# FPGA_FLASH_EEPROM.net
KiCad netlist of a schematic drawn in Altium Designer
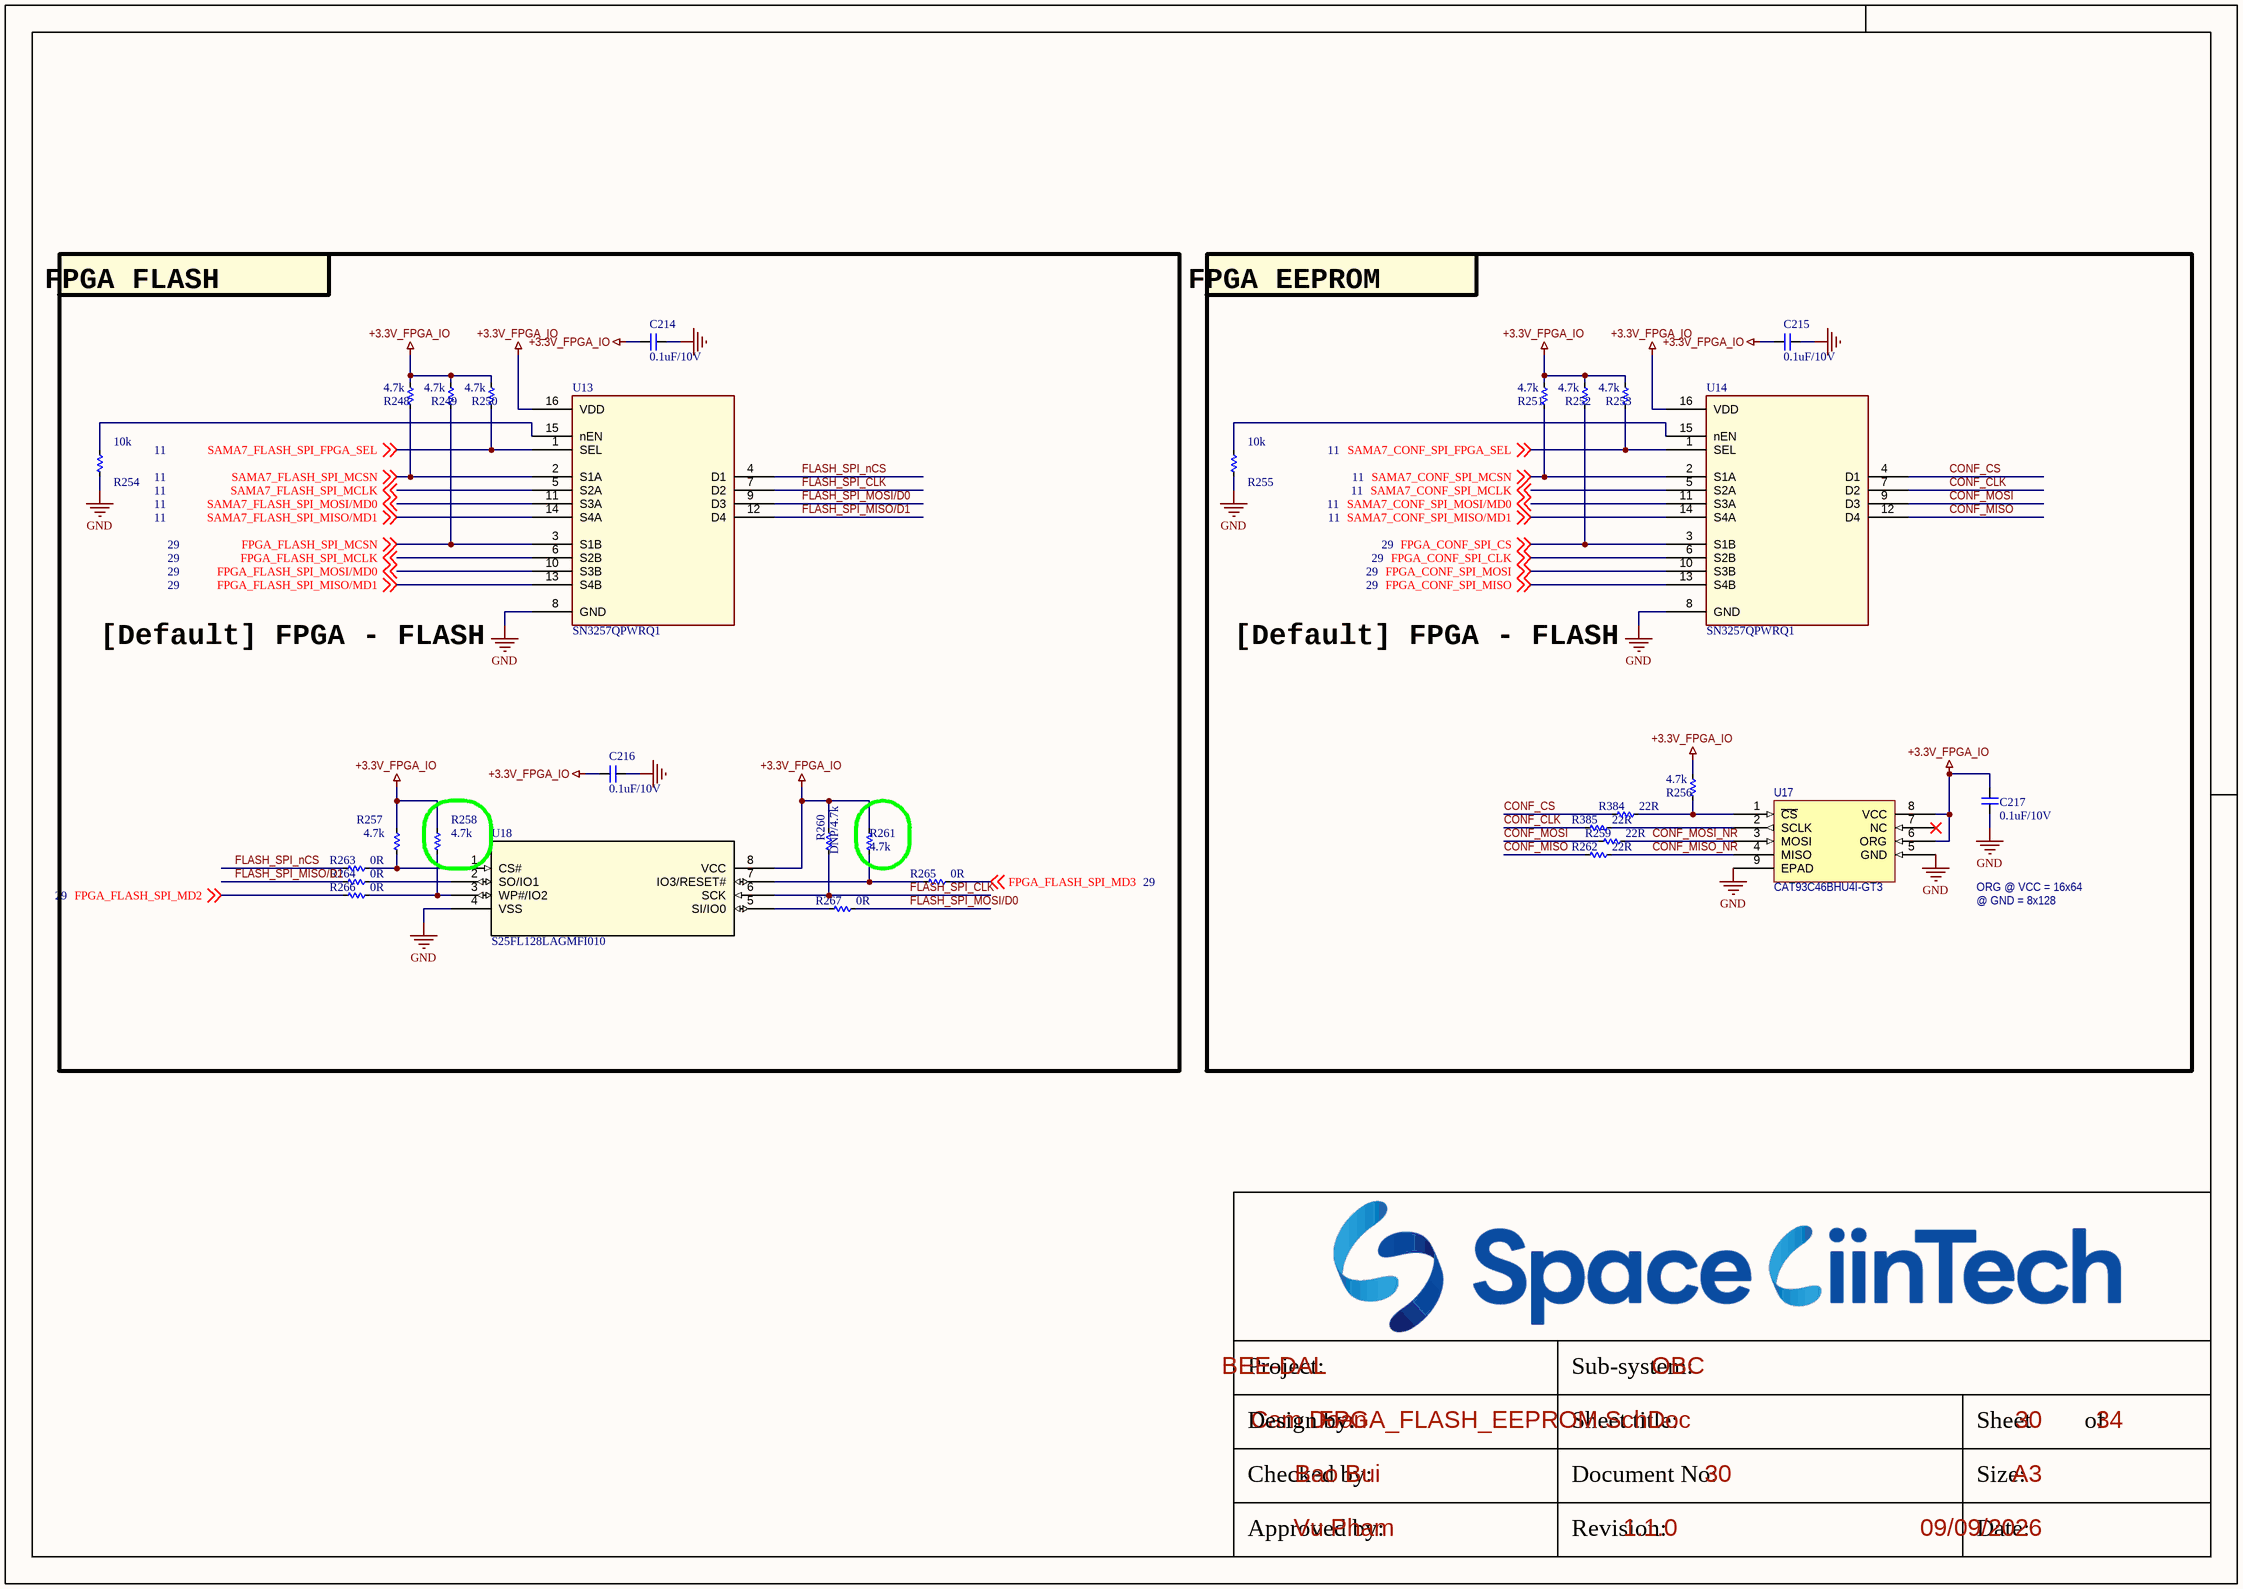
[diagram p0: FPGA_FLASH_EEPROM.SchDoc]

(export (version "E")
  (design (tool "Eeschema 10.0.6"))
  (components
    (comp (ref "C214")
      (value "0.1uF/10V")
      (footprint "CAP_C_1005X50_L")
      (description "CAP")
      (libsource (lib "LABLIB") (part "_CAP_C_2"))
    )
    (comp (ref "C215")
      (value "0.1uF/10V")
      (footprint "CAP_C_1005X50_L")
      (description "CAP")
      (libsource (lib "LABLIB") (part "_CAP_C_2"))
    )
    (comp (ref "C216")
      (value "0.1uF/10V")
      (footprint "CAP_C_1005X50_L")
      (description "CAP")
      (libsource (lib "LABLIB") (part "_CAP_C_2"))
    )
    (comp (ref "C217")
      (value "0.1uF/10V")
      (footprint "CAP_C_1005X50_L")
      (description "CAP")
      (libsource (lib "LABLIB") (part "_CAP_C_2"))
    )
    (comp (ref "R248")
      (value "4.7k")
      (footprint "RES_C_1005x30_L")
      (description "RES")
      (libsource (lib "IFBschelib") (part "_RES_B_2"))
    )
    (comp (ref "R249")
      (value "4.7k")
      (footprint "RES_C_1005x30_L")
      (description "RES")
      (libsource (lib "IFBschelib") (part "_RES_B_2"))
    )
    (comp (ref "R250")
      (value "4.7k")
      (footprint "RES_C_1005x30_L")
      (description "RES")
      (libsource (lib "IFBschelib") (part "_RES_B_2"))
    )
    (comp (ref "R251")
      (value "4.7k")
      (footprint "RES_C_1005x30_L")
      (description "RES")
      (libsource (lib "IFBschelib") (part "_RES_B_2"))
    )
    (comp (ref "R252")
      (value "4.7k")
      (footprint "RES_C_1005x30_L")
      (description "RES")
      (libsource (lib "IFBschelib") (part "_RES_B_2"))
    )
    (comp (ref "R253")
      (value "4.7k")
      (footprint "RES_C_1005x30_L")
      (description "RES")
      (libsource (lib "IFBschelib") (part "_RES_B_2"))
    )
    (comp (ref "R254")
      (value "10k")
      (footprint "RES_C_1005x30_L")
      (description "RES")
      (libsource (lib "LABLIB") (part "_RES_B_2"))
    )
    (comp (ref "R255")
      (value "10k")
      (footprint "RES_C_1005x30_L")
      (description "RES")
      (libsource (lib "LABLIB") (part "_RES_B_2"))
    )
    (comp (ref "R256")
      (value "4.7k")
      (footprint "RES_C_1005x30_L")
      (description "RES")
      (libsource (lib "IFBschelib") (part "_RES_B_2"))
    )
    (comp (ref "R257")
      (value "4.7k")
      (footprint "RES_C_1005x30_L")
      (description "RES")
      (libsource (lib "IFBschelib") (part "_RES_B_2"))
    )
    (comp (ref "R258")
      (value "4.7k")
      (footprint "RES_C_1005x30_L")
      (description "RES")
      (libsource (lib "IFBschelib") (part "_RES_B_2"))
    )
    (comp (ref "R259")
      (value "22R")
      (footprint "RES_C_1005x30_L")
      (description "RES")
      (libsource (lib "IFBschelib") (part "_RES_B_2"))
    )
    (comp (ref "R260")
      (value "DNP/4.7k")
      (footprint "RES_C_1005x30_L")
      (description "RES")
      (libsource (lib "IFBschelib") (part "_RES_B_2"))
    )
    (comp (ref "R261")
      (value "4.7k")
      (footprint "RES_C_1005x30_L")
      (description "RES")
      (libsource (lib "IFBschelib") (part "_RES_B_2"))
    )
    (comp (ref "R262")
      (value "22R")
      (footprint "RES_C_1005x30_L")
      (description "RES")
      (libsource (lib "IFBschelib") (part "_RES_B_2"))
    )
    (comp (ref "R263")
      (value "0R")
      (footprint "RES_C_1005x30_L")
      (description "RES")
      (libsource (lib "LABLIB") (part "_RES_B_2"))
    )
    (comp (ref "R264")
      (value "0R")
      (footprint "RES_C_1005x30_L")
      (description "RES")
      (libsource (lib "LABLIB") (part "_RES_B_2"))
    )
    (comp (ref "R265")
      (value "0R")
      (footprint "RES_C_1005x30_L")
      (description "RES")
      (libsource (lib "LABLIB") (part "_RES_B_2"))
    )
    (comp (ref "R266")
      (value "0R")
      (footprint "RES_C_1005x30_L")
      (description "RES")
      (libsource (lib "LABLIB") (part "_RES_B_2"))
    )
    (comp (ref "R267")
      (value "0R")
      (footprint "RES_C_1005x30_L")
      (description "RES")
      (libsource (lib "LABLIB") (part "_RES_B_2"))
    )
    (comp (ref "R384")
      (value "22R")
      (footprint "RES_C_1005x30_L")
      (description "RES")
      (libsource (lib "IFBschelib") (part "_RES_B_2"))
    )
    (comp (ref "R385")
      (value "22R")
      (footprint "RES_C_1005x30_L")
      (description "RES")
      (libsource (lib "IFBschelib") (part "_RES_B_2"))
    )
    (comp (ref "U13")
      (value "SN3257QPWRQ1")
      (footprint "SOIC_PRQ1_TEX")
      (fields (field (name "COPYRIGHT") "Copyright (C) 2025 Ultra Librarian. All rights reserved."))
      (libsource (lib "LABLIB") (part "IC_SW_SPI_SN3257QPWRQ1"))
    )
    (comp (ref "U14")
      (value "SN3257QPWRQ1")
      (footprint "SOIC_PRQ1_TEX")
      (fields (field (name "COPYRIGHT") "Copyright (C) 2025 Ultra Librarian. All rights reserved."))
      (libsource (lib "LABLIB") (part "IC_SW_SPI_SN3257QPWRQ1"))
    )
    (comp (ref "U17")
      (value "CAT93C46BHU4I-GT3")
      (footprint "CAT93C46BHU4I-GT3")
      (description "EEPROM Memory IC 1Kb (128 x 8, 64 x 16) SPI 4 MHz 8-UDFN-EP (2x3)")
      (libsource (lib "Virtex") (part "CAT93C46BHU4I-GT3"))
    )
    (comp (ref "U18")
      (value "S25FL128LAGMFI010")
      (footprint "SOIC8_S25FL_CYP")
      (description "Description")
      (fields (field (name "COPYRIGHT") "Copyright (C) 2025 Ultra Librarian. All rights reserved."))
      (libsource (lib "IFBschelib") (part "S25FL128LAGMFI010"))
    )
  )
  (nets
    (net (code "1") (name "+3.3V_FPGA_IO") (class "Default")
      (node (ref "C214") (pin "2") (pinfunction "2_2") (pintype "passive"))
      (node (ref "C215") (pin "2") (pinfunction "2_2") (pintype "passive"))
      (node (ref "C216") (pin "2") (pinfunction "2_2") (pintype "passive"))
      (node (ref "C217") (pin "1") (pinfunction "1_1") (pintype "passive"))
      (node (ref "R248") (pin "2") (pinfunction "2_2") (pintype "passive"))
      (node (ref "R249") (pin "2") (pinfunction "2_2") (pintype "passive"))
      (node (ref "R250") (pin "2") (pinfunction "2_2") (pintype "passive"))
      (node (ref "R251") (pin "2") (pinfunction "2_2") (pintype "passive"))
      (node (ref "R252") (pin "2") (pinfunction "2_2") (pintype "passive"))
      (node (ref "R253") (pin "2") (pinfunction "2_2") (pintype "passive"))
      (node (ref "R256") (pin "2") (pinfunction "2_2") (pintype "passive"))
      (node (ref "R257") (pin "2") (pinfunction "2_2") (pintype "passive"))
      (node (ref "R258") (pin "2") (pinfunction "2_2") (pintype "passive"))
      (node (ref "R260") (pin "2") (pinfunction "2_2") (pintype "passive"))
      (node (ref "R261") (pin "2") (pinfunction "2_2") (pintype "passive"))
      (node (ref "U13") (pin "16") (pinfunction "VDD_16") (pintype "passive"))
      (node (ref "U14") (pin "16") (pinfunction "VDD_16") (pintype "passive"))
      (node (ref "U17") (pin "6") (pinfunction "ORG_6") (pintype "input"))
      (node (ref "U17") (pin "8") (pinfunction "VCC_8") (pintype "power_in"))
      (node (ref "U18") (pin "8") (pinfunction "VCC_8") (pintype "power_in"))
    )
    (net (code "2") (name "/CONF_CLK") (class "Default")
      (node (ref "R385") (pin "2") (pinfunction "2_2") (pintype "passive"))
      (node (ref "U14") (pin "7") (pinfunction "D2_7") (pintype "passive"))
    )
    (net (code "3") (name "/CONF_CS") (class "Default")
      (node (ref "R384") (pin "2") (pinfunction "2_2") (pintype "passive"))
      (node (ref "U14") (pin "4") (pinfunction "D1_4") (pintype "passive"))
    )
    (net (code "4") (name "/CONF_MISO") (class "Default")
      (node (ref "R262") (pin "2") (pinfunction "2_2") (pintype "passive"))
      (node (ref "U14") (pin "12") (pinfunction "D4_12") (pintype "passive"))
    )
    (net (code "5") (name "/CONF_MISO_NR") (class "Default")
      (node (ref "R262") (pin "1") (pinfunction "1_1") (pintype "passive"))
      (node (ref "U17") (pin "4") (pinfunction "MISO_4") (pintype "power_in"))
    )
    (net (code "6") (name "/CONF_MOSI") (class "Default")
      (node (ref "R259") (pin "2") (pinfunction "2_2") (pintype "passive"))
      (node (ref "U14") (pin "9") (pinfunction "D3_9") (pintype "passive"))
    )
    (net (code "7") (name "/CONF_MOSI_NR") (class "Default")
      (node (ref "R259") (pin "1") (pinfunction "1_1") (pintype "passive"))
      (node (ref "U17") (pin "3") (pinfunction "MOSI_3") (pintype "input"))
    )
    (net (code "8") (name "/FLASH_SPI_CLK") (class "Default")
      (node (ref "R260") (pin "1") (pinfunction "1_1") (pintype "passive"))
      (node (ref "U13") (pin "7") (pinfunction "D2_7") (pintype "passive"))
      (node (ref "U18") (pin "6") (pinfunction "SCK_6") (pintype "input"))
    )
    (net (code "9") (name "/FLASH_SPI_MISO{slash}D1") (class "Default")
      (node (ref "R264") (pin "1") (pinfunction "1_1") (pintype "passive"))
      (node (ref "U13") (pin "12") (pinfunction "D4_12") (pintype "passive"))
    )
    (net (code "10") (name "/FLASH_SPI_MOSI{slash}D0") (class "Default")
      (node (ref "R267") (pin "2") (pinfunction "2_2") (pintype "passive"))
      (node (ref "U13") (pin "9") (pinfunction "D3_9") (pintype "passive"))
    )
    (net (code "11") (name "/FLASH_SPI_nCS") (class "Default")
      (node (ref "R263") (pin "1") (pinfunction "1_1") (pintype "passive"))
      (node (ref "U13") (pin "4") (pinfunction "D1_4") (pintype "passive"))
    )
    (net (code "12") (name "FPGA_CONF_SPI_CLK") (class "Default")
      (node (ref "U14") (pin "6") (pinfunction "S2B_6") (pintype "passive"))
    )
    (net (code "13") (name "FPGA_CONF_SPI_CS") (class "Default")
      (node (ref "R252") (pin "1") (pinfunction "1_1") (pintype "passive"))
      (node (ref "U14") (pin "3") (pinfunction "S1B_3") (pintype "passive"))
    )
    (net (code "14") (name "FPGA_CONF_SPI_MISO") (class "Default")
      (node (ref "U14") (pin "13") (pinfunction "S4B_13") (pintype "passive"))
    )
    (net (code "15") (name "FPGA_CONF_SPI_MOSI") (class "Default")
      (node (ref "U14") (pin "10") (pinfunction "S3B_10") (pintype "passive"))
    )
    (net (code "16") (name "FPGA_FLASH_SPI_MCLK") (class "Default")
      (node (ref "U13") (pin "6") (pinfunction "S2B_6") (pintype "passive"))
    )
    (net (code "17") (name "FPGA_FLASH_SPI_MCSN") (class "Default")
      (node (ref "R249") (pin "1") (pinfunction "1_1") (pintype "passive"))
      (node (ref "U13") (pin "3") (pinfunction "S1B_3") (pintype "passive"))
    )
    (net (code "18") (name "FPGA_FLASH_SPI_MD2") (class "Default")
      (node (ref "R266") (pin "1") (pinfunction "1_1") (pintype "passive"))
    )
    (net (code "19") (name "FPGA_FLASH_SPI_MD3") (class "Default")
      (node (ref "R265") (pin "2") (pinfunction "2_2") (pintype "passive"))
    )
    (net (code "20") (name "FPGA_FLASH_SPI_MISO{slash}MD1") (class "Default")
      (node (ref "U13") (pin "13") (pinfunction "S4B_13") (pintype "passive"))
    )
    (net (code "21") (name "FPGA_FLASH_SPI_MOSI{slash}MD0") (class "Default")
      (node (ref "U13") (pin "10") (pinfunction "S3B_10") (pintype "passive"))
    )
    (net (code "22") (name "GND") (class "Default")
      (node (ref "C214") (pin "1") (pinfunction "1_1") (pintype "passive"))
      (node (ref "C215") (pin "1") (pinfunction "1_1") (pintype "passive"))
      (node (ref "C216") (pin "1") (pinfunction "1_1") (pintype "passive"))
      (node (ref "C217") (pin "2") (pinfunction "2_2") (pintype "passive"))
      (node (ref "R254") (pin "1") (pinfunction "1_1") (pintype "passive"))
      (node (ref "R255") (pin "1") (pinfunction "1_1") (pintype "passive"))
      (node (ref "U13") (pin "8") (pinfunction "GND_8") (pintype "passive"))
      (node (ref "U14") (pin "8") (pinfunction "GND_8") (pintype "passive"))
      (node (ref "U17") (pin "5") (pinfunction "GND_5") (pintype "input"))
      (node (ref "U17") (pin "9") (pinfunction "EPAD_9") (pintype "power_in"))
      (node (ref "U18") (pin "4") (pinfunction "VSS_4") (pintype "power_in"))
    )
    (net (code "23") (name "Net-(U13-nEN)") (class "Default")
      (node (ref "R254") (pin "2") (pinfunction "2_2") (pintype "passive"))
      (node (ref "U13") (pin "15") (pinfunction "nEN_15") (pintype "passive"))
    )
    (net (code "24") (name "Net-(U14-nEN)") (class "Default")
      (node (ref "R255") (pin "2") (pinfunction "2_2") (pintype "passive"))
      (node (ref "U14") (pin "15") (pinfunction "nEN_15") (pintype "passive"))
    )
    (net (code "25") (name "Net-(U17-SCLK)") (class "Default")
      (node (ref "R385") (pin "1") (pinfunction "1_1") (pintype "passive"))
      (node (ref "U17") (pin "2") (pinfunction "SCLK_2") (pintype "output"))
    )
    (net (code "26") (name "Net-(U17-~{CS})") (class "Default")
      (node (ref "R256") (pin "1") (pinfunction "1_1") (pintype "passive"))
      (node (ref "R384") (pin "1") (pinfunction "1_1") (pintype "passive"))
      (node (ref "U17") (pin "1") (pinfunction "~{CS}_1") (pintype "input"))
    )
    (net (code "27") (name "Net-(U18-CS#)") (class "Default")
      (node (ref "R257") (pin "1") (pinfunction "1_1") (pintype "passive"))
      (node (ref "R263") (pin "2") (pinfunction "2_2") (pintype "passive"))
      (node (ref "U18") (pin "1") (pinfunction "CS#_1") (pintype "input"))
    )
    (net (code "28") (name "Net-(U18-IO3{slash}RESET#)") (class "Default")
      (node (ref "R261") (pin "1") (pinfunction "1_1") (pintype "passive"))
      (node (ref "R265") (pin "1") (pinfunction "1_1") (pintype "passive"))
      (node (ref "U18") (pin "7") (pinfunction "IO3/RESET#_7") (pintype "bidirectional"))
    )
    (net (code "29") (name "Net-(U18-SI{slash}IO0)") (class "Default")
      (node (ref "R267") (pin "1") (pinfunction "1_1") (pintype "passive"))
      (node (ref "U18") (pin "5") (pinfunction "SI/IO0_5") (pintype "bidirectional"))
    )
    (net (code "30") (name "Net-(U18-SO{slash}IO1)") (class "Default")
      (node (ref "R264") (pin "2") (pinfunction "2_2") (pintype "passive"))
      (node (ref "U18") (pin "2") (pinfunction "SO/IO1_2") (pintype "bidirectional"))
    )
    (net (code "31") (name "Net-(U18-WP#{slash}IO2)") (class "Default")
      (node (ref "R258") (pin "1") (pinfunction "1_1") (pintype "passive"))
      (node (ref "R266") (pin "2") (pinfunction "2_2") (pintype "passive"))
      (node (ref "U18") (pin "3") (pinfunction "WP#/IO2_3") (pintype "bidirectional"))
    )
    (net (code "32") (name "SAMA7_CONF_SPI_FPGA_SEL") (class "Default")
      (node (ref "R253") (pin "1") (pinfunction "1_1") (pintype "passive"))
      (node (ref "U14") (pin "1") (pinfunction "SEL_1") (pintype "passive"))
    )
    (net (code "33") (name "SAMA7_CONF_SPI_MCLK") (class "Default")
      (node (ref "U14") (pin "5") (pinfunction "S2A_5") (pintype "passive"))
    )
    (net (code "34") (name "SAMA7_CONF_SPI_MCSN") (class "Default")
      (node (ref "R251") (pin "1") (pinfunction "1_1") (pintype "passive"))
      (node (ref "U14") (pin "2") (pinfunction "S1A_2") (pintype "passive"))
    )
    (net (code "35") (name "SAMA7_CONF_SPI_MISO{slash}MD1") (class "Default")
      (node (ref "U14") (pin "14") (pinfunction "S4A_14") (pintype "passive"))
    )
    (net (code "36") (name "SAMA7_CONF_SPI_MOSI{slash}MD0") (class "Default")
      (node (ref "U14") (pin "11") (pinfunction "S3A_11") (pintype "passive"))
    )
    (net (code "37") (name "SAMA7_FLASH_SPI_FPGA_SEL") (class "Default")
      (node (ref "R250") (pin "1") (pinfunction "1_1") (pintype "passive"))
      (node (ref "U13") (pin "1") (pinfunction "SEL_1") (pintype "passive"))
    )
    (net (code "38") (name "SAMA7_FLASH_SPI_MCLK") (class "Default")
      (node (ref "U13") (pin "5") (pinfunction "S2A_5") (pintype "passive"))
    )
    (net (code "39") (name "SAMA7_FLASH_SPI_MCSN") (class "Default")
      (node (ref "R248") (pin "1") (pinfunction "1_1") (pintype "passive"))
      (node (ref "U13") (pin "2") (pinfunction "S1A_2") (pintype "passive"))
    )
    (net (code "40") (name "SAMA7_FLASH_SPI_MISO{slash}MD1") (class "Default")
      (node (ref "U13") (pin "14") (pinfunction "S4A_14") (pintype "passive"))
    )
    (net (code "41") (name "SAMA7_FLASH_SPI_MOSI{slash}MD0") (class "Default")
      (node (ref "U13") (pin "11") (pinfunction "S3A_11") (pintype "passive"))
    )
    (net (code "42") (name "unconnected-(U17-NC-Pad7)") (class "Default")
      (node (ref "U17") (pin "7") (pinfunction "NC_7") (pintype "input+no_connect"))
    )
  )
)
